# differential_amplifier.net
KiCad netlist of a schematic drawn in EAGLE
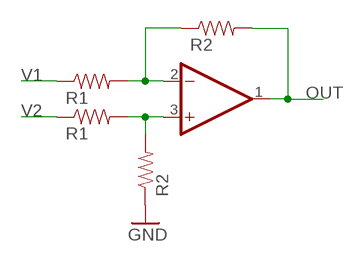
[diagram p0: schematic, sheet 1]

(export (version "E")
  (design (tool "Eeschema 10.0.6"))
  (components
    (comp (ref "IC1")
      (value "MCP6022")
      (footprint "eagle-import:SOIC8_150MIL")
      (libsource (lib "eagle-import") (part "MCP6022"))
    )
    (comp (ref "R1")
      (value "R1")
      (footprint "eagle-import:0402-RES")
      (libsource (lib "eagle-import") (part "RESISTOR0402-RES"))
    )
    (comp (ref "R2")
      (value "R1")
      (footprint "eagle-import:0402-RES")
      (libsource (lib "eagle-import") (part "RESISTOR0402-RES"))
    )
    (comp (ref "R3")
      (value "R2")
      (footprint "eagle-import:0402-RES")
      (libsource (lib "eagle-import") (part "RESISTOR0402-RES"))
    )
    (comp (ref "R4")
      (value "R2")
      (footprint "eagle-import:0402-RES")
      (libsource (lib "eagle-import") (part "RESISTOR0402-RES"))
    )
  )
  (nets
    (net (code "1") (name "/OUT") (class "Default")
      (node (ref "IC1") (pin "1") (pinfunction "OUT_1") (pintype "output"))
      (node (ref "R3") (pin "2") (pinfunction "2_2") (pintype "passive"))
    )
    (net (code "2") (name "/V1") (class "Default")
      (node (ref "R1") (pin "1") (pinfunction "1_1") (pintype "passive"))
    )
    (net (code "3") (name "/V2") (class "Default")
      (node (ref "R2") (pin "1") (pinfunction "1_1") (pintype "passive"))
    )
    (net (code "4") (name "GND") (class "Default")
      (node (ref "R4") (pin "1") (pinfunction "1_1") (pintype "passive"))
    )
    (net (code "5") (name "Net-(IC1A-+IN)") (class "Default")
      (node (ref "IC1") (pin "3") (pinfunction "+IN_3") (pintype "input"))
      (node (ref "R2") (pin "2") (pinfunction "2_2") (pintype "passive"))
      (node (ref "R4") (pin "2") (pinfunction "2_2") (pintype "passive"))
    )
    (net (code "6") (name "Net-(IC1A--IN)") (class "Default")
      (node (ref "IC1") (pin "2") (pinfunction "-IN_2") (pintype "input"))
      (node (ref "R1") (pin "2") (pinfunction "2_2") (pintype "passive"))
      (node (ref "R3") (pin "1") (pinfunction "1_1") (pintype "passive"))
    )
  )
)
